# led-breakout.net
KiCad netlist of a schematic drawn in EAGLE
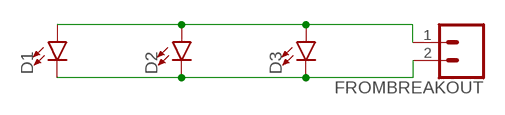
[diagram p0: schematic, sheet 1]

(export (version "E")
  (design (tool "Eeschema 10.0.6"))
  (components
    (comp (ref "D1")
      (value "LED3MM")
      (footprint "eagle-import:LED_3MM")
      (libsource (lib "eagle-import") (part "LED3MM"))
    )
    (comp (ref "D2")
      (value "LED3MM")
      (footprint "eagle-import:LED_3MM")
      (libsource (lib "eagle-import") (part "LED3MM"))
    )
    (comp (ref "D3")
      (value "LED3MM")
      (footprint "eagle-import:LED_3MM")
      (libsource (lib "eagle-import") (part "LED3MM"))
    )
    (comp (ref "FROMBREAKOUT")
      (value "CONN_021X02_NO_SILK")
      (footprint "eagle-import:1X02_NO_SILK")
      (libsource (lib "eagle-import") (part "CONN_021X02_NO_SILK"))
    )
  )
  (nets
    (net (code "1") (name "Net-(D1-C)") (class "Default")
      (node (ref "D1") (pin "K") (pinfunction "C_K") (pintype "passive"))
      (node (ref "D2") (pin "K") (pinfunction "C_K") (pintype "passive"))
      (node (ref "D3") (pin "K") (pinfunction "C_K") (pintype "passive"))
      (node (ref "FROMBREAKOUT") (pin "2") (pinfunction "2_2") (pintype "passive"))
    )
    (net (code "2") (name "Net-(D1-PadA)") (class "Default")
      (node (ref "D1") (pin "A") (pinfunction "A_A") (pintype "passive"))
      (node (ref "D2") (pin "A") (pinfunction "A_A") (pintype "passive"))
      (node (ref "D3") (pin "A") (pinfunction "A_A") (pintype "passive"))
      (node (ref "FROMBREAKOUT") (pin "1") (pinfunction "1_1") (pintype "passive"))
    )
  )
)
